# breakout.net
KiCad netlist of a schematic drawn in EAGLE
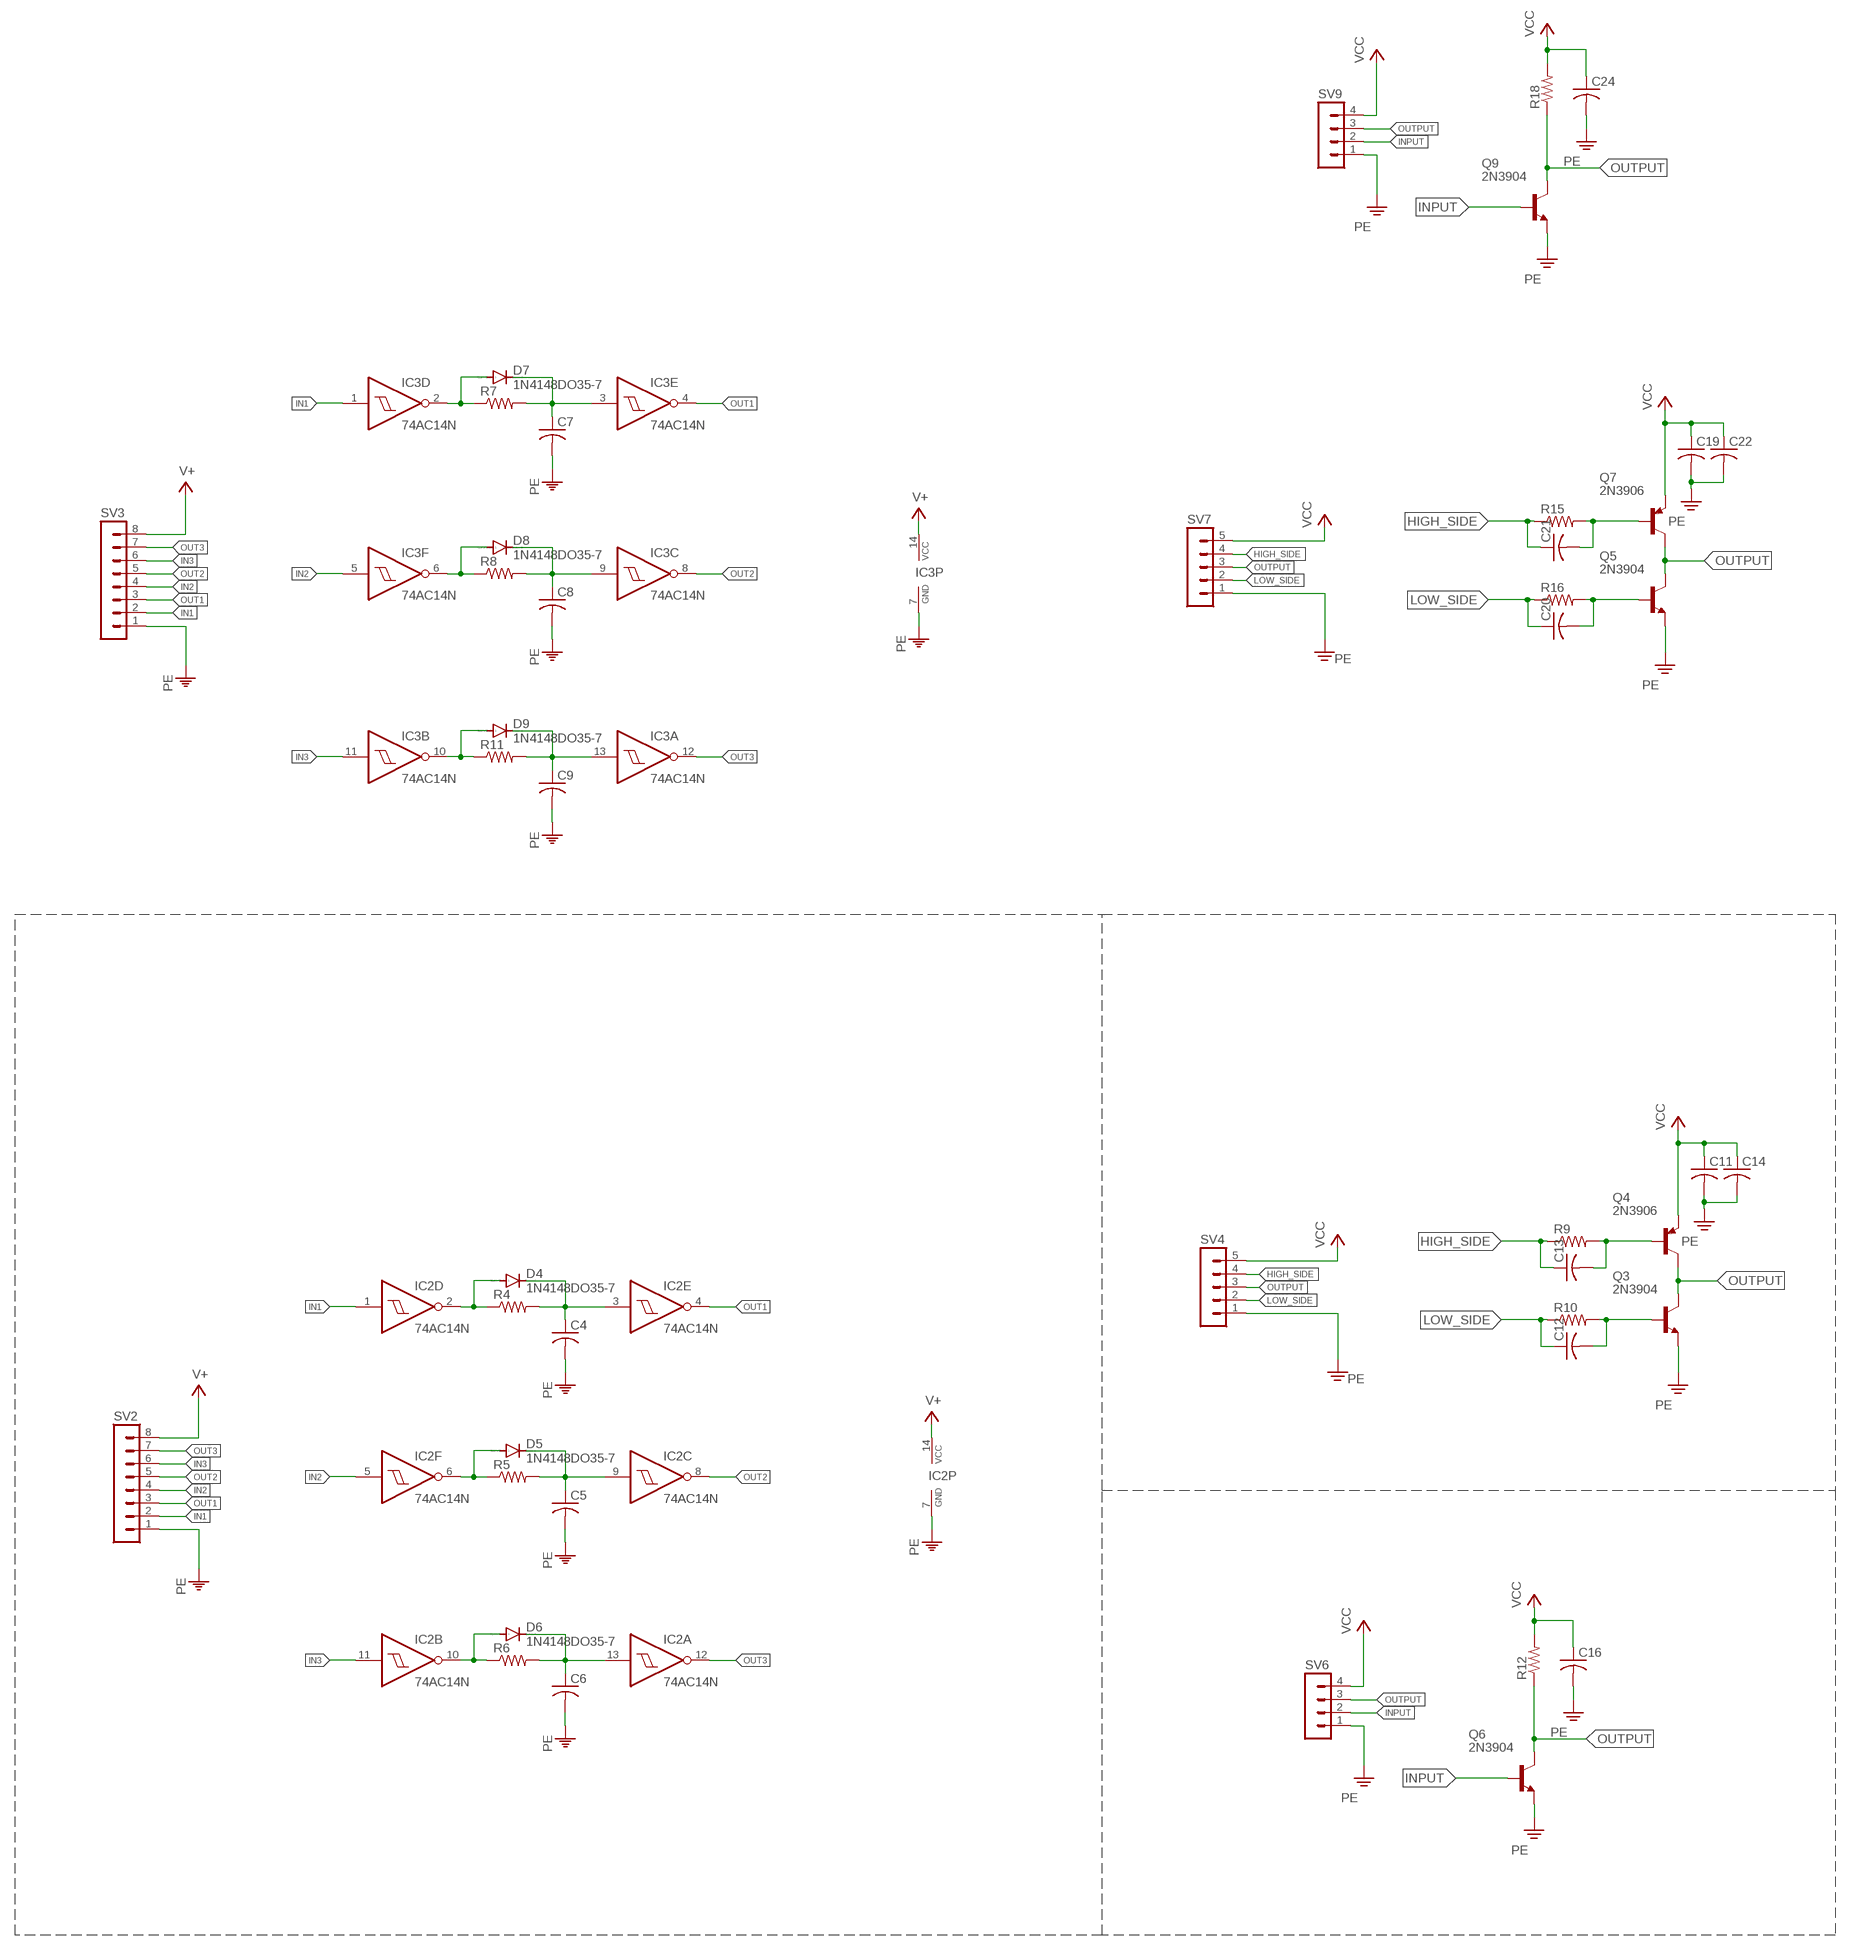
[diagram p0: schematic, sheet 1]

(export (version "E")
  (design (tool "Eeschema 10.0.6"))
  (components
    (comp (ref "C4")
      (value "C-US025-025X050")
      (footprint "eagle-import:C025-025X050")
      (libsource (lib "eagle-import") (part "C-US025-025X050"))
    )
    (comp (ref "C5")
      (value "C-US025-025X050")
      (footprint "eagle-import:C025-025X050")
      (libsource (lib "eagle-import") (part "C-US025-025X050"))
    )
    (comp (ref "C6")
      (value "C-US025-025X050")
      (footprint "eagle-import:C025-025X050")
      (libsource (lib "eagle-import") (part "C-US025-025X050"))
    )
    (comp (ref "C7")
      (value "C-US025-025X050")
      (footprint "eagle-import:C025-025X050")
      (libsource (lib "eagle-import") (part "C-US025-025X050"))
    )
    (comp (ref "C8")
      (value "C-US025-025X050")
      (footprint "eagle-import:C025-025X050")
      (libsource (lib "eagle-import") (part "C-US025-025X050"))
    )
    (comp (ref "C9")
      (value "C-US025-025X050")
      (footprint "eagle-import:C025-025X050")
      (libsource (lib "eagle-import") (part "C-US025-025X050"))
    )
    (comp (ref "C11")
      (value "C-US050-024X044")
      (footprint "eagle-import:C050-024X044")
      (libsource (lib "eagle-import") (part "C-US050-024X044"))
    )
    (comp (ref "C12")
      (value "C-US050-024X044")
      (footprint "eagle-import:C050-024X044")
      (libsource (lib "eagle-import") (part "C-US050-024X044"))
    )
    (comp (ref "C13")
      (value "C-US050-024X044")
      (footprint "eagle-import:C050-024X044")
      (libsource (lib "eagle-import") (part "C-US050-024X044"))
    )
    (comp (ref "C14")
      (value "C-US050-024X044")
      (footprint "eagle-import:C050-024X044")
      (libsource (lib "eagle-import") (part "C-US050-024X044"))
    )
    (comp (ref "C16")
      (value "C-US025-030X050")
      (footprint "eagle-import:C025-030X050")
      (libsource (lib "eagle-import") (part "C-US025-030X050"))
    )
    (comp (ref "C19")
      (value "C-US050-024X044")
      (footprint "eagle-import:C050-024X044")
      (libsource (lib "eagle-import") (part "C-US050-024X044"))
    )
    (comp (ref "C20")
      (value "C-US050-024X044")
      (footprint "eagle-import:C050-024X044")
      (libsource (lib "eagle-import") (part "C-US050-024X044"))
    )
    (comp (ref "C21")
      (value "C-US050-024X044")
      (footprint "eagle-import:C050-024X044")
      (libsource (lib "eagle-import") (part "C-US050-024X044"))
    )
    (comp (ref "C22")
      (value "C-US050-024X044")
      (footprint "eagle-import:C050-024X044")
      (libsource (lib "eagle-import") (part "C-US050-024X044"))
    )
    (comp (ref "C24")
      (value "C-US025-030X050")
      (footprint "eagle-import:C025-030X050")
      (libsource (lib "eagle-import") (part "C-US025-030X050"))
    )
    (comp (ref "D4")
      (value "1N4148DO35-7")
      (footprint "eagle-import:DO35-7")
      (libsource (lib "eagle-import") (part "1N4148DO35-7"))
    )
    (comp (ref "D5")
      (value "1N4148DO35-7")
      (footprint "eagle-import:DO35-7")
      (libsource (lib "eagle-import") (part "1N4148DO35-7"))
    )
    (comp (ref "D6")
      (value "1N4148DO35-7")
      (footprint "eagle-import:DO35-7")
      (libsource (lib "eagle-import") (part "1N4148DO35-7"))
    )
    (comp (ref "D7")
      (value "1N4148DO35-7")
      (footprint "eagle-import:DO35-7")
      (libsource (lib "eagle-import") (part "1N4148DO35-7"))
    )
    (comp (ref "D8")
      (value "1N4148DO35-7")
      (footprint "eagle-import:DO35-7")
      (libsource (lib "eagle-import") (part "1N4148DO35-7"))
    )
    (comp (ref "D9")
      (value "1N4148DO35-7")
      (footprint "eagle-import:DO35-7")
      (libsource (lib "eagle-import") (part "1N4148DO35-7"))
    )
    (comp (ref "IC2")
      (value "74AC14N")
      (footprint "eagle-import:DIL14")
      (libsource (lib "eagle-import") (part "7414NAC"))
    )
    (comp (ref "IC3")
      (value "74AC14N")
      (footprint "eagle-import:DIL14")
      (libsource (lib "eagle-import") (part "7414NAC"))
    )
    (comp (ref "Q3")
      (value "2N3904")
      (footprint "eagle-import:TO-92")
      (libsource (lib "eagle-import") (part "2N3904"))
    )
    (comp (ref "Q4")
      (value "2N3906")
      (footprint "eagle-import:TO-92")
      (libsource (lib "eagle-import") (part "2N3906"))
    )
    (comp (ref "Q5")
      (value "2N3904")
      (footprint "eagle-import:TO-92")
      (libsource (lib "eagle-import") (part "2N3904"))
    )
    (comp (ref "Q6")
      (value "2N3904")
      (footprint "eagle-import:TO-92")
      (libsource (lib "eagle-import") (part "2N3904"))
    )
    (comp (ref "Q7")
      (value "2N3906")
      (footprint "eagle-import:TO-92")
      (libsource (lib "eagle-import") (part "2N3906"))
    )
    (comp (ref "Q9")
      (value "2N3904")
      (footprint "eagle-import:TO-92")
      (libsource (lib "eagle-import") (part "2N3904"))
    )
    (comp (ref "R4")
      (value "R-US_0204/7")
      (footprint "eagle-import:0204_7")
      (libsource (lib "eagle-import") (part "R-US_0204/7"))
    )
    (comp (ref "R5")
      (value "R-US_0204/7")
      (footprint "eagle-import:0204_7")
      (libsource (lib "eagle-import") (part "R-US_0204/7"))
    )
    (comp (ref "R6")
      (value "R-US_0204/7")
      (footprint "eagle-import:0204_7")
      (libsource (lib "eagle-import") (part "R-US_0204/7"))
    )
    (comp (ref "R7")
      (value "R-US_0204/7")
      (footprint "eagle-import:0204_7")
      (libsource (lib "eagle-import") (part "R-US_0204/7"))
    )
    (comp (ref "R8")
      (value "R-US_0204/7")
      (footprint "eagle-import:0204_7")
      (libsource (lib "eagle-import") (part "R-US_0204/7"))
    )
    (comp (ref "R9")
      (value "R-US_0204/5")
      (footprint "eagle-import:0204_5")
      (libsource (lib "eagle-import") (part "R-US_0204/5"))
    )
    (comp (ref "R10")
      (value "R-US_0204/5")
      (footprint "eagle-import:0204_5")
      (libsource (lib "eagle-import") (part "R-US_0204/5"))
    )
    (comp (ref "R11")
      (value "R-US_0204/7")
      (footprint "eagle-import:0204_7")
      (libsource (lib "eagle-import") (part "R-US_0204/7"))
    )
    (comp (ref "R12")
      (value "R-US_0204/7")
      (footprint "eagle-import:0204_7")
      (libsource (lib "eagle-import") (part "R-US_0204/7"))
    )
    (comp (ref "R15")
      (value "R-US_0204/5")
      (footprint "eagle-import:0204_5")
      (libsource (lib "eagle-import") (part "R-US_0204/5"))
    )
    (comp (ref "R16")
      (value "R-US_0204/5")
      (footprint "eagle-import:0204_5")
      (libsource (lib "eagle-import") (part "R-US_0204/5"))
    )
    (comp (ref "R18")
      (value "R-US_0204/7")
      (footprint "eagle-import:0204_7")
      (libsource (lib "eagle-import") (part "R-US_0204/7"))
    )
    (comp (ref "SV2")
      (value "MA08-1")
      (footprint "eagle-import:MA08-1")
      (libsource (lib "eagle-import") (part "MA08-1"))
    )
    (comp (ref "SV3")
      (value "MA08-1")
      (footprint "eagle-import:MA08-1")
      (libsource (lib "eagle-import") (part "MA08-1"))
    )
    (comp (ref "SV4")
      (value "MA05-1")
      (footprint "eagle-import:MA05-1")
      (libsource (lib "eagle-import") (part "MA05-1"))
    )
    (comp (ref "SV6")
      (value "MA04-1")
      (footprint "eagle-import:MA04-1")
      (libsource (lib "eagle-import") (part "MA04-1"))
    )
    (comp (ref "SV7")
      (value "MA05-1")
      (footprint "eagle-import:MA05-1")
      (libsource (lib "eagle-import") (part "MA05-1"))
    )
    (comp (ref "SV9")
      (value "MA04-1")
      (footprint "eagle-import:MA04-1")
      (libsource (lib "eagle-import") (part "MA04-1"))
    )
  )
  (nets
    (net (code "1") (name "HIGH_SIDE") (class "Default")
      (node (ref "C13") (pin "1") (pinfunction "1_1") (pintype "passive"))
      (node (ref "C21") (pin "1") (pinfunction "1_1") (pintype "passive"))
      (node (ref "R15") (pin "1") (pinfunction "1_1") (pintype "passive"))
      (node (ref "R9") (pin "1") (pinfunction "1_1") (pintype "passive"))
      (node (ref "SV4") (pin "4") (pinfunction "4_4") (pintype "passive"))
      (node (ref "SV7") (pin "4") (pinfunction "4_4") (pintype "passive"))
    )
    (net (code "2") (name "IN1") (class "Default")
      (node (ref "IC2") (pin "1") (pinfunction "I_1") (pintype "input"))
      (node (ref "IC3") (pin "1") (pinfunction "I_1") (pintype "input"))
      (node (ref "SV2") (pin "2") (pinfunction "2_2") (pintype "passive"))
      (node (ref "SV3") (pin "2") (pinfunction "2_2") (pintype "passive"))
    )
    (net (code "3") (name "IN2") (class "Default")
      (node (ref "IC2") (pin "5") (pinfunction "I_5") (pintype "input"))
      (node (ref "IC3") (pin "5") (pinfunction "I_5") (pintype "input"))
      (node (ref "SV2") (pin "4") (pinfunction "4_4") (pintype "passive"))
      (node (ref "SV3") (pin "4") (pinfunction "4_4") (pintype "passive"))
    )
    (net (code "4") (name "IN3") (class "Default")
      (node (ref "IC2") (pin "11") (pinfunction "I_11") (pintype "input"))
      (node (ref "IC3") (pin "11") (pinfunction "I_11") (pintype "input"))
      (node (ref "SV2") (pin "6") (pinfunction "6_6") (pintype "passive"))
      (node (ref "SV3") (pin "6") (pinfunction "6_6") (pintype "passive"))
    )
    (net (code "5") (name "INPUT") (class "Default")
      (node (ref "Q6") (pin "B") (pinfunction "B_B") (pintype "passive"))
      (node (ref "Q9") (pin "B") (pinfunction "B_B") (pintype "passive"))
      (node (ref "SV6") (pin "2") (pinfunction "2_2") (pintype "passive"))
      (node (ref "SV9") (pin "2") (pinfunction "2_2") (pintype "passive"))
    )
    (net (code "6") (name "LOW_SIDE") (class "Default")
      (node (ref "C12") (pin "1") (pinfunction "1_1") (pintype "passive"))
      (node (ref "C20") (pin "1") (pinfunction "1_1") (pintype "passive"))
      (node (ref "R10") (pin "1") (pinfunction "1_1") (pintype "passive"))
      (node (ref "R16") (pin "1") (pinfunction "1_1") (pintype "passive"))
      (node (ref "SV4") (pin "2") (pinfunction "2_2") (pintype "passive"))
      (node (ref "SV7") (pin "2") (pinfunction "2_2") (pintype "passive"))
    )
    (net (code "7") (name "Net-(C12-Pad2)") (class "Default")
      (node (ref "C12") (pin "2") (pinfunction "2_2") (pintype "passive"))
      (node (ref "Q3") (pin "B") (pinfunction "B_B") (pintype "passive"))
      (node (ref "R10") (pin "2") (pinfunction "2_2") (pintype "passive"))
    )
    (net (code "8") (name "Net-(C13-Pad2)") (class "Default")
      (node (ref "C13") (pin "2") (pinfunction "2_2") (pintype "passive"))
      (node (ref "Q4") (pin "B") (pinfunction "B_B") (pintype "passive"))
      (node (ref "R9") (pin "2") (pinfunction "2_2") (pintype "passive"))
    )
    (net (code "9") (name "Net-(C20-Pad2)") (class "Default")
      (node (ref "C20") (pin "2") (pinfunction "2_2") (pintype "passive"))
      (node (ref "Q5") (pin "B") (pinfunction "B_B") (pintype "passive"))
      (node (ref "R16") (pin "2") (pinfunction "2_2") (pintype "passive"))
    )
    (net (code "10") (name "Net-(C21-Pad2)") (class "Default")
      (node (ref "C21") (pin "2") (pinfunction "2_2") (pintype "passive"))
      (node (ref "Q7") (pin "B") (pinfunction "B_B") (pintype "passive"))
      (node (ref "R15") (pin "2") (pinfunction "2_2") (pintype "passive"))
    )
    (net (code "11") (name "Net-(IC2A-I)") (class "Default")
      (node (ref "C6") (pin "1") (pinfunction "1_1") (pintype "passive"))
      (node (ref "D6") (pin "C") (pinfunction "C_C") (pintype "passive"))
      (node (ref "IC2") (pin "13") (pinfunction "I_13") (pintype "input"))
      (node (ref "R6") (pin "2") (pinfunction "2_2") (pintype "passive"))
    )
    (net (code "12") (name "Net-(IC2B-O)") (class "Default")
      (node (ref "D6") (pin "A") (pinfunction "A_A") (pintype "passive"))
      (node (ref "IC2") (pin "10") (pinfunction "O_10") (pintype "output"))
      (node (ref "R6") (pin "1") (pinfunction "1_1") (pintype "passive"))
    )
    (net (code "13") (name "Net-(IC2C-I)") (class "Default")
      (node (ref "C5") (pin "1") (pinfunction "1_1") (pintype "passive"))
      (node (ref "D5") (pin "C") (pinfunction "C_C") (pintype "passive"))
      (node (ref "IC2") (pin "9") (pinfunction "I_9") (pintype "input"))
      (node (ref "R5") (pin "2") (pinfunction "2_2") (pintype "passive"))
    )
    (net (code "14") (name "Net-(IC2D-O)") (class "Default")
      (node (ref "D4") (pin "A") (pinfunction "A_A") (pintype "passive"))
      (node (ref "IC2") (pin "2") (pinfunction "O_2") (pintype "output"))
      (node (ref "R4") (pin "1") (pinfunction "1_1") (pintype "passive"))
    )
    (net (code "15") (name "Net-(IC2E-I)") (class "Default")
      (node (ref "C4") (pin "1") (pinfunction "1_1") (pintype "passive"))
      (node (ref "D4") (pin "C") (pinfunction "C_C") (pintype "passive"))
      (node (ref "IC2") (pin "3") (pinfunction "I_3") (pintype "input"))
      (node (ref "R4") (pin "2") (pinfunction "2_2") (pintype "passive"))
    )
    (net (code "16") (name "Net-(IC2F-O)") (class "Default")
      (node (ref "D5") (pin "A") (pinfunction "A_A") (pintype "passive"))
      (node (ref "IC2") (pin "6") (pinfunction "O_6") (pintype "output"))
      (node (ref "R5") (pin "1") (pinfunction "1_1") (pintype "passive"))
    )
    (net (code "17") (name "Net-(IC3A-I)") (class "Default")
      (node (ref "C9") (pin "1") (pinfunction "1_1") (pintype "passive"))
      (node (ref "D9") (pin "C") (pinfunction "C_C") (pintype "passive"))
      (node (ref "IC3") (pin "13") (pinfunction "I_13") (pintype "input"))
      (node (ref "R11") (pin "2") (pinfunction "2_2") (pintype "passive"))
    )
    (net (code "18") (name "Net-(IC3B-O)") (class "Default")
      (node (ref "D9") (pin "A") (pinfunction "A_A") (pintype "passive"))
      (node (ref "IC3") (pin "10") (pinfunction "O_10") (pintype "output"))
      (node (ref "R11") (pin "1") (pinfunction "1_1") (pintype "passive"))
    )
    (net (code "19") (name "Net-(IC3C-I)") (class "Default")
      (node (ref "C8") (pin "1") (pinfunction "1_1") (pintype "passive"))
      (node (ref "D8") (pin "C") (pinfunction "C_C") (pintype "passive"))
      (node (ref "IC3") (pin "9") (pinfunction "I_9") (pintype "input"))
      (node (ref "R8") (pin "2") (pinfunction "2_2") (pintype "passive"))
    )
    (net (code "20") (name "Net-(IC3D-O)") (class "Default")
      (node (ref "D7") (pin "A") (pinfunction "A_A") (pintype "passive"))
      (node (ref "IC3") (pin "2") (pinfunction "O_2") (pintype "output"))
      (node (ref "R7") (pin "1") (pinfunction "1_1") (pintype "passive"))
    )
    (net (code "21") (name "Net-(IC3E-I)") (class "Default")
      (node (ref "C7") (pin "1") (pinfunction "1_1") (pintype "passive"))
      (node (ref "D7") (pin "C") (pinfunction "C_C") (pintype "passive"))
      (node (ref "IC3") (pin "3") (pinfunction "I_3") (pintype "input"))
      (node (ref "R7") (pin "2") (pinfunction "2_2") (pintype "passive"))
    )
    (net (code "22") (name "Net-(IC3F-O)") (class "Default")
      (node (ref "D8") (pin "A") (pinfunction "A_A") (pintype "passive"))
      (node (ref "IC3") (pin "6") (pinfunction "O_6") (pintype "output"))
      (node (ref "R8") (pin "1") (pinfunction "1_1") (pintype "passive"))
    )
    (net (code "23") (name "OUT1") (class "Default")
      (node (ref "IC2") (pin "4") (pinfunction "O_4") (pintype "output"))
      (node (ref "IC3") (pin "4") (pinfunction "O_4") (pintype "output"))
      (node (ref "SV2") (pin "3") (pinfunction "3_3") (pintype "passive"))
      (node (ref "SV3") (pin "3") (pinfunction "3_3") (pintype "passive"))
    )
    (net (code "24") (name "OUT2") (class "Default")
      (node (ref "IC2") (pin "8") (pinfunction "O_8") (pintype "output"))
      (node (ref "IC3") (pin "8") (pinfunction "O_8") (pintype "output"))
      (node (ref "SV2") (pin "5") (pinfunction "5_5") (pintype "passive"))
      (node (ref "SV3") (pin "5") (pinfunction "5_5") (pintype "passive"))
    )
    (net (code "25") (name "OUT3") (class "Default")
      (node (ref "IC2") (pin "12") (pinfunction "O_12") (pintype "output"))
      (node (ref "IC3") (pin "12") (pinfunction "O_12") (pintype "output"))
      (node (ref "SV2") (pin "7") (pinfunction "7_7") (pintype "passive"))
      (node (ref "SV3") (pin "7") (pinfunction "7_7") (pintype "passive"))
    )
    (net (code "26") (name "OUTPUT") (class "Default")
      (node (ref "Q3") (pin "C") (pinfunction "C_C") (pintype "passive"))
      (node (ref "Q4") (pin "C") (pinfunction "C_C") (pintype "passive"))
      (node (ref "Q5") (pin "C") (pinfunction "C_C") (pintype "passive"))
      (node (ref "Q6") (pin "C") (pinfunction "C_C") (pintype "passive"))
      (node (ref "Q7") (pin "C") (pinfunction "C_C") (pintype "passive"))
      (node (ref "Q9") (pin "C") (pinfunction "C_C") (pintype "passive"))
      (node (ref "R12") (pin "1") (pinfunction "1_1") (pintype "passive"))
      (node (ref "R18") (pin "1") (pinfunction "1_1") (pintype "passive"))
      (node (ref "SV4") (pin "3") (pinfunction "3_3") (pintype "passive"))
      (node (ref "SV6") (pin "3") (pinfunction "3_3") (pintype "passive"))
      (node (ref "SV7") (pin "3") (pinfunction "3_3") (pintype "passive"))
      (node (ref "SV9") (pin "3") (pinfunction "3_3") (pintype "passive"))
    )
    (net (code "27") (name "PE") (class "Default")
      (node (ref "C11") (pin "2") (pinfunction "2_2") (pintype "passive"))
      (node (ref "C14") (pin "2") (pinfunction "2_2") (pintype "passive"))
      (node (ref "C16") (pin "2") (pinfunction "2_2") (pintype "passive"))
      (node (ref "C19") (pin "2") (pinfunction "2_2") (pintype "passive"))
      (node (ref "C22") (pin "2") (pinfunction "2_2") (pintype "passive"))
      (node (ref "C24") (pin "2") (pinfunction "2_2") (pintype "passive"))
      (node (ref "C4") (pin "2") (pinfunction "2_2") (pintype "passive"))
      (node (ref "C5") (pin "2") (pinfunction "2_2") (pintype "passive"))
      (node (ref "C6") (pin "2") (pinfunction "2_2") (pintype "passive"))
      (node (ref "C7") (pin "2") (pinfunction "2_2") (pintype "passive"))
      (node (ref "C8") (pin "2") (pinfunction "2_2") (pintype "passive"))
      (node (ref "C9") (pin "2") (pinfunction "2_2") (pintype "passive"))
      (node (ref "IC2") (pin "7") (pinfunction "GND_7") (pintype "power_in"))
      (node (ref "IC3") (pin "7") (pinfunction "GND_7") (pintype "power_in"))
      (node (ref "Q3") (pin "E") (pinfunction "E_E") (pintype "passive"))
      (node (ref "Q5") (pin "E") (pinfunction "E_E") (pintype "passive"))
      (node (ref "Q6") (pin "E") (pinfunction "E_E") (pintype "passive"))
      (node (ref "Q9") (pin "E") (pinfunction "E_E") (pintype "passive"))
      (node (ref "SV2") (pin "1") (pinfunction "1_1") (pintype "passive"))
      (node (ref "SV3") (pin "1") (pinfunction "1_1") (pintype "passive"))
      (node (ref "SV4") (pin "1") (pinfunction "1_1") (pintype "passive"))
      (node (ref "SV6") (pin "1") (pinfunction "1_1") (pintype "passive"))
      (node (ref "SV7") (pin "1") (pinfunction "1_1") (pintype "passive"))
      (node (ref "SV9") (pin "1") (pinfunction "1_1") (pintype "passive"))
    )
    (net (code "28") (name "V+") (class "Default")
      (node (ref "IC2") (pin "14") (pinfunction "VCC_14") (pintype "power_in"))
      (node (ref "IC3") (pin "14") (pinfunction "VCC_14") (pintype "power_in"))
      (node (ref "SV2") (pin "8") (pinfunction "8_8") (pintype "passive"))
      (node (ref "SV3") (pin "8") (pinfunction "8_8") (pintype "passive"))
    )
    (net (code "29") (name "VCC") (class "Default")
      (node (ref "C11") (pin "1") (pinfunction "1_1") (pintype "passive"))
      (node (ref "C14") (pin "1") (pinfunction "1_1") (pintype "passive"))
      (node (ref "C16") (pin "1") (pinfunction "1_1") (pintype "passive"))
      (node (ref "C19") (pin "1") (pinfunction "1_1") (pintype "passive"))
      (node (ref "C22") (pin "1") (pinfunction "1_1") (pintype "passive"))
      (node (ref "C24") (pin "1") (pinfunction "1_1") (pintype "passive"))
      (node (ref "Q4") (pin "E") (pinfunction "E_E") (pintype "passive"))
      (node (ref "Q7") (pin "E") (pinfunction "E_E") (pintype "passive"))
      (node (ref "R12") (pin "2") (pinfunction "2_2") (pintype "passive"))
      (node (ref "R18") (pin "2") (pinfunction "2_2") (pintype "passive"))
      (node (ref "SV4") (pin "5") (pinfunction "5_5") (pintype "passive"))
      (node (ref "SV6") (pin "4") (pinfunction "4_4") (pintype "passive"))
      (node (ref "SV7") (pin "5") (pinfunction "5_5") (pintype "passive"))
      (node (ref "SV9") (pin "4") (pinfunction "4_4") (pintype "passive"))
    )
  )
)
